# Sheet_1_2025-08-11.net
KiCad netlist of a schematic drawn in Altium Designer
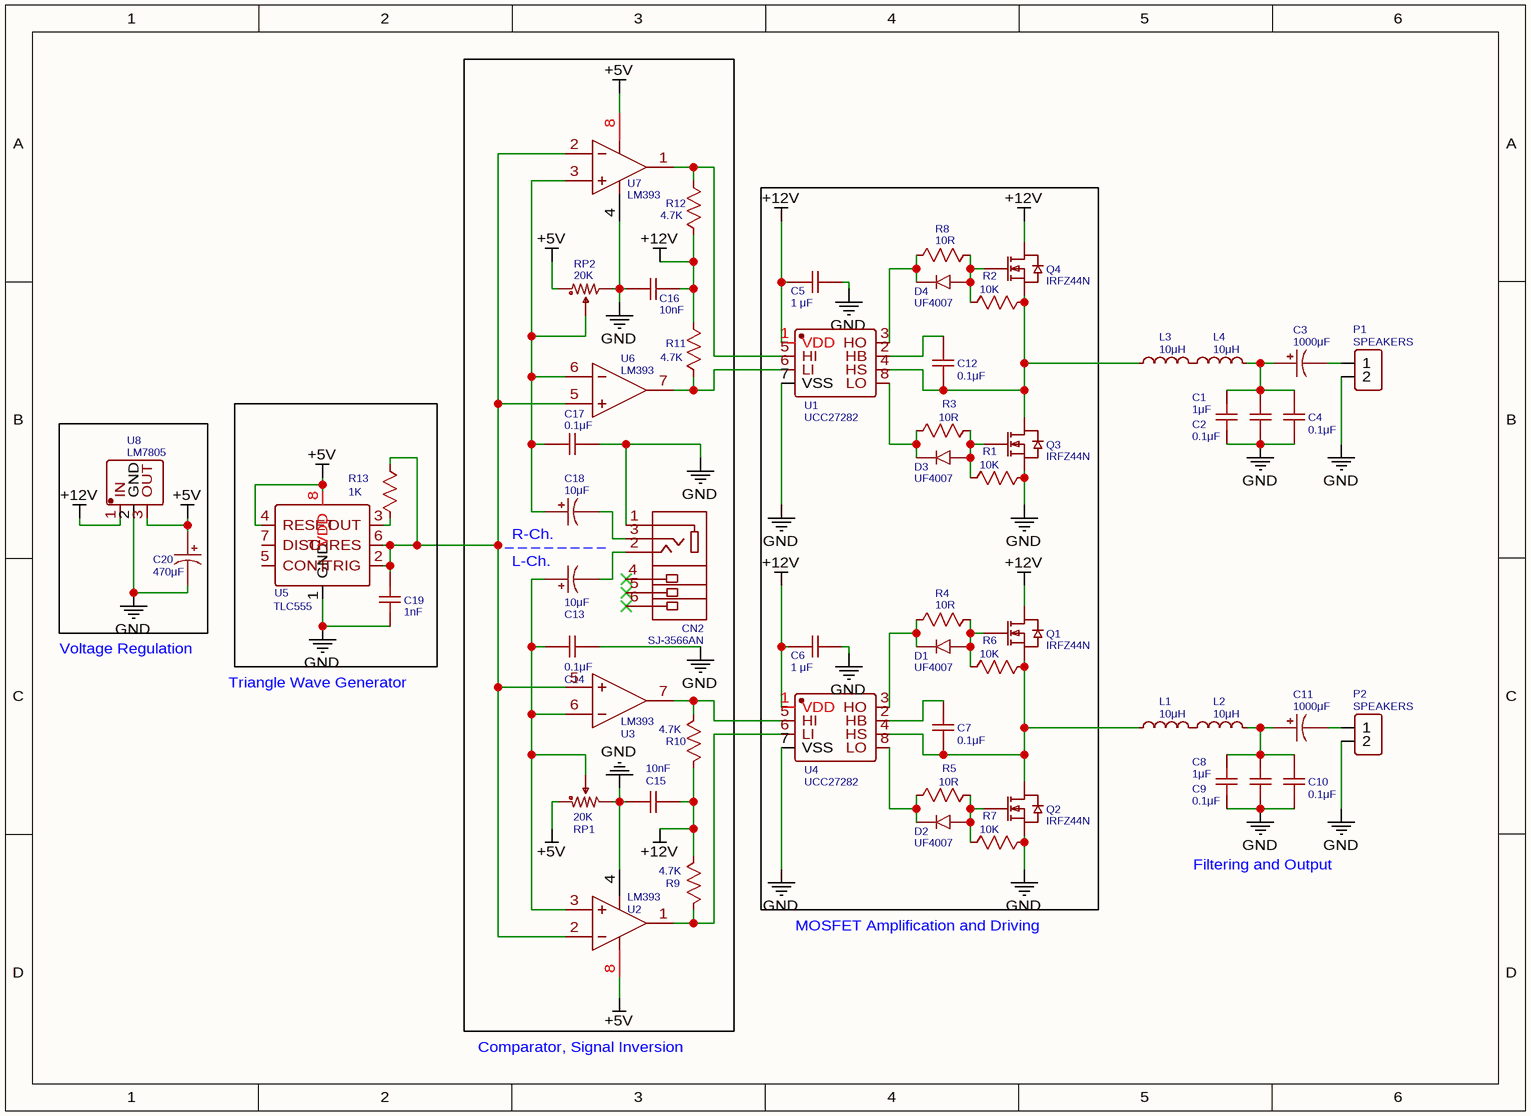
[diagram p0: Sheet_1_2025-08-11.schdoc]

(export (version "E")
  (design (tool "Eeschema 10.0.6"))
  (components
    (comp (ref "C1")
      (value "1μF")
      (fields (field (name "CONTRIBUTOR") "LCEDA_Lib"))
      (libsource (lib "altium-import") (part "root_3_1μF_"))
    )
    (comp (ref "C2")
      (value "0.1μF")
      (fields (field (name "CONTRIBUTOR") "LCEDA_Lib"))
      (libsource (lib "altium-import") (part "root_3_0.1μF_"))
    )
    (comp (ref "C3")
      (value "1000μF")
      (fields (field (name "CONTRIBUTOR") "LCEDA_Lib"))
      (libsource (lib "altium-import") (part "root_0_1000μF_"))
    )
    (comp (ref "C4")
      (value "0.1μF")
      (fields (field (name "CONTRIBUTOR") "LCEDA_Lib"))
      (libsource (lib "altium-import") (part "root_1_0.1μF_"))
    )
    (comp (ref "C5")
      (value "1 μF")
      (fields (field (name "CONTRIBUTOR") "LCEDA_Lib"))
      (libsource (lib "altium-import") (part "root_0_1 μF_"))
    )
    (comp (ref "C6")
      (value "1 μF")
      (fields (field (name "CONTRIBUTOR") "LCEDA_Lib"))
      (libsource (lib "altium-import") (part "root_0_1 μF_"))
    )
    (comp (ref "C7")
      (value "0.1μF")
      (fields (field (name "CONTRIBUTOR") "LCEDA_Lib"))
      (libsource (lib "altium-import") (part "root_1_0.1μF_"))
    )
    (comp (ref "C8")
      (value "1μF")
      (fields (field (name "CONTRIBUTOR") "LCEDA_Lib"))
      (libsource (lib "altium-import") (part "root_3_1μF_"))
    )
    (comp (ref "C9")
      (value "0.1μF")
      (fields (field (name "CONTRIBUTOR") "LCEDA_Lib"))
      (libsource (lib "altium-import") (part "root_3_0.1μF_"))
    )
    (comp (ref "C10")
      (value "0.1μF")
      (fields (field (name "CONTRIBUTOR") "LCEDA_Lib"))
      (libsource (lib "altium-import") (part "root_1_0.1μF_"))
    )
    (comp (ref "C11")
      (value "1000μF")
      (fields (field (name "CONTRIBUTOR") "LCEDA_Lib"))
      (libsource (lib "altium-import") (part "root_0_1000μF_"))
    )
    (comp (ref "C12")
      (value "0.1μF")
      (fields (field (name "CONTRIBUTOR") "LCEDA_Lib"))
      (libsource (lib "altium-import") (part "root_1_0.1μF_"))
    )
    (comp (ref "C13")
      (value "10μF")
      (fields (field (name "CONTRIBUTOR") "LCEDA_Lib"))
      (libsource (lib "") (part "root_0_10μF__1"))
    )
    (comp (ref "C14")
      (value "0.1μF")
      (fields (field (name "CONTRIBUTOR") "LCEDA_Lib"))
      (libsource (lib "altium-import") (part "root_2_0.1μF_"))
    )
    (comp (ref "C15")
      (value "10nF")
      (fields (field (name "CONTRIBUTOR") "LCEDA_Lib"))
      (libsource (lib "") (part "root_2_10nF__1"))
    )
    (comp (ref "C16")
      (value "10nF")
      (fields (field (name "CONTRIBUTOR") "LCEDA_Lib"))
      (libsource (lib "altium-import") (part "root_2_10nF_"))
    )
    (comp (ref "C17")
      (value "0.1μF")
      (fields (field (name "CONTRIBUTOR") "LCEDA_Lib"))
      (libsource (lib "") (part "root_2_0.1μF__1"))
    )
    (comp (ref "C18")
      (value "10μF")
      (fields (field (name "CONTRIBUTOR") "LCEDA_Lib"))
      (libsource (lib "altium-import") (part "root_0_10μF_"))
    )
    (comp (ref "C19")
      (value "1nF")
      (fields (field (name "CONTRIBUTOR") "LCEDA_Lib"))
      (libsource (lib "altium-import") (part "root_1_1nF_"))
    )
    (comp (ref "C20")
      (value "470μF")
      (fields (field (name "CONTRIBUTOR") "LCEDA_Lib"))
      (libsource (lib "altium-import") (part "root_3_470μF_"))
    )
    (comp (ref "CN2")
      (value "SJ-3566AN")
      (fields (field (name "MANUFACTURER") "CUI") (field (name "CONTRIBUTOR") "lcsc"))
      (libsource (lib "altium-import") (part "root_0_SJ-3566AN_"))
    )
    (comp (ref "D1")
      (value "UF4007")
      (fields (field (name "MANUFACTURER") "STARSEA") (field (name "CONTRIBUTOR") "立创EDA官方封装库"))
      (libsource (lib "altium-import") (part "root_2_UF4007_"))
    )
    (comp (ref "D2")
      (value "UF4007")
      (fields (field (name "MANUFACTURER") "STARSEA") (field (name "CONTRIBUTOR") "立创EDA官方封装库"))
      (libsource (lib "altium-import") (part "root_2_UF4007_"))
    )
    (comp (ref "D3")
      (value "UF4007")
      (fields (field (name "MANUFACTURER") "STARSEA") (field (name "CONTRIBUTOR") "立创EDA官方封装库"))
      (libsource (lib "altium-import") (part "root_2_UF4007_"))
    )
    (comp (ref "D4")
      (value "UF4007")
      (fields (field (name "MANUFACTURER") "STARSEA") (field (name "CONTRIBUTOR") "立创EDA官方封装库"))
      (libsource (lib "altium-import") (part "root_2_UF4007_"))
    )
    (comp (ref "L1")
      (value "10μH")
      (fields (field (name "CONTRIBUTOR") "LCEDA_Lib"))
      (libsource (lib "altium-import") (part "root_0_10μH_"))
    )
    (comp (ref "L2")
      (value "10μH")
      (fields (field (name "CONTRIBUTOR") "LCEDA_Lib"))
      (libsource (lib "altium-import") (part "root_0_10μH_"))
    )
    (comp (ref "L3")
      (value "10μH")
      (fields (field (name "CONTRIBUTOR") "LCEDA_Lib"))
      (libsource (lib "altium-import") (part "root_0_10μH_"))
    )
    (comp (ref "L4")
      (value "10μH")
      (fields (field (name "CONTRIBUTOR") "LCEDA_Lib"))
      (libsource (lib "altium-import") (part "root_0_10μH_"))
    )
    (comp (ref "P1")
      (value "SPEAKERS")
      (fields (field (name "CONTRIBUTOR") "LCEDA_Lib"))
      (libsource (lib "altium-import") (part "root_0_SPEAKERS_"))
    )
    (comp (ref "P2")
      (value "SPEAKERS")
      (fields (field (name "CONTRIBUTOR") "LCEDA_Lib"))
      (libsource (lib "altium-import") (part "root_0_SPEAKERS_"))
    )
    (comp (ref "Q1")
      (value "IRFZ44N")
      (fields (field (name "MANUFACTURER") "IR") (field (name "MANUFACTURER PART") "IRFZ44NPBF"))
      (libsource (lib "altium-import") (part "root_0_IRFZ44N_"))
    )
    (comp (ref "Q2")
      (value "IRFZ44N")
      (fields (field (name "MANUFACTURER") "IR") (field (name "MANUFACTURER PART") "IRFZ44NPBF"))
      (libsource (lib "altium-import") (part "root_0_IRFZ44N_"))
    )
    (comp (ref "Q3")
      (value "IRFZ44N")
      (fields (field (name "MANUFACTURER") "IR") (field (name "MANUFACTURER PART") "IRFZ44NPBF"))
      (libsource (lib "altium-import") (part "root_0_IRFZ44N_"))
    )
    (comp (ref "Q4")
      (value "IRFZ44N")
      (fields (field (name "MANUFACTURER") "IR") (field (name "MANUFACTURER PART") "IRFZ44NPBF"))
      (libsource (lib "altium-import") (part "root_0_IRFZ44N_"))
    )
    (comp (ref "R1")
      (value "10K")
      (fields (field (name "CONTRIBUTOR") "LCEDA_Lib"))
      (libsource (lib "altium-import") (part "root_0_10K_"))
    )
    (comp (ref "R2")
      (value "10K")
      (fields (field (name "CONTRIBUTOR") "LCEDA_Lib"))
      (libsource (lib "altium-import") (part "root_0_10K_"))
    )
    (comp (ref "R3")
      (value "10R")
      (fields (field (name "CONTRIBUTOR") "LCEDA_Lib"))
      (libsource (lib "altium-import") (part "root_2_10R_"))
    )
    (comp (ref "R4")
      (value "10R")
      (fields (field (name "CONTRIBUTOR") "LCEDA_Lib"))
      (libsource (lib "altium-import") (part "root_2_10R_"))
    )
    (comp (ref "R5")
      (value "10R")
      (fields (field (name "CONTRIBUTOR") "LCEDA_Lib"))
      (libsource (lib "altium-import") (part "root_2_10R_"))
    )
    (comp (ref "R6")
      (value "10K")
      (fields (field (name "CONTRIBUTOR") "LCEDA_Lib"))
      (libsource (lib "altium-import") (part "root_0_10K_"))
    )
    (comp (ref "R7")
      (value "10K")
      (fields (field (name "CONTRIBUTOR") "LCEDA_Lib"))
      (libsource (lib "altium-import") (part "root_0_10K_"))
    )
    (comp (ref "R8")
      (value "10R")
      (fields (field (name "CONTRIBUTOR") "LCEDA_Lib"))
      (libsource (lib "altium-import") (part "root_2_10R_"))
    )
    (comp (ref "R9")
      (value "4.7K")
      (fields (field (name "CONTRIBUTOR") "LCEDA_Lib"))
      (libsource (lib "") (part "root_3_4.7K__1"))
    )
    (comp (ref "R10")
      (value "4.7K")
      (fields (field (name "CONTRIBUTOR") "LCEDA_Lib"))
      (libsource (lib "") (part "root_3_4.7K__1"))
    )
    (comp (ref "R11")
      (value "4.7K")
      (fields (field (name "CONTRIBUTOR") "LCEDA_Lib"))
      (libsource (lib "altium-import") (part "root_3_4.7K_"))
    )
    (comp (ref "R12")
      (value "4.7K")
      (fields (field (name "CONTRIBUTOR") "LCEDA_Lib"))
      (libsource (lib "altium-import") (part "root_3_4.7K_"))
    )
    (comp (ref "R13")
      (value "1K")
      (fields (field (name "CONTRIBUTOR") "LCEDA_Lib"))
      (libsource (lib "altium-import") (part "root_1_1K_"))
    )
    (comp (ref "RP1")
      (value "20K")
      (fields (field (name "CONTRIBUTOR") "LCEDA_Lib"))
      (libsource (lib "") (part "root_2_20K__1"))
    )
    (comp (ref "RP2")
      (value "20K")
      (fields (field (name "CONTRIBUTOR") "LCEDA_Lib"))
      (libsource (lib "altium-import") (part "root_2_20K_"))
    )
    (comp (ref "U1")
      (value "UCC27282")
      (fields
        (field (name "MANUFACTURER") "Texas Instruments")
        (field (name "MANUFACTURER PART") "UCC27200DR")
        (field (name "CONTRIBUTOR") "Electric_Evan")
      )
      (libsource (lib "altium-import") (part "root_0_UCC27282_"))
    )
    (comp (ref "U2")
      (value "LM393")
      (fields
        (field (name "MANUFACTURER") "TI")
        (field (name "MANUFACTURER PART") "LM393P")
        (field (name "SUBPART_NO") "1")
      )
      (libsource (lib "altium-import") (part "root_0_LM393_"))
    )
    (comp (ref "U3")
      (value "LM393")
      (fields
        (field (name "MANUFACTURER") "TI")
        (field (name "MANUFACTURER PART") "LM393P")
        (field (name "SUBPART_NO") "1")
      )
      (libsource (lib "") (part "root_0_LM393__2"))
    )
    (comp (ref "U4")
      (value "UCC27282")
      (fields
        (field (name "MANUFACTURER") "Texas Instruments")
        (field (name "MANUFACTURER PART") "UCC27200DR")
        (field (name "CONTRIBUTOR") "Electric_Evan")
      )
      (libsource (lib "altium-import") (part "root_0_UCC27282_"))
    )
    (comp (ref "U5")
      (value "TLC555")
      (fields
        (field (name "MANUFACTURER") "TI(德州仪器)")
        (field (name "MANUFACTURER PART") "TLC555CP")
        (field (name "CONTRIBUTOR") "Electric_Evan")
      )
      (libsource (lib "altium-import") (part "root_0_TLC555_"))
    )
    (comp (ref "U6")
      (value "LM393")
      (fields
        (field (name "MANUFACTURER") "TI")
        (field (name "MANUFACTURER PART") "LM393P")
        (field (name "SUBPART_NO") "1")
      )
      (libsource (lib "") (part "root_0_LM393__3"))
    )
    (comp (ref "U7")
      (value "LM393")
      (fields
        (field (name "MANUFACTURER") "TI")
        (field (name "MANUFACTURER PART") "LM393P")
        (field (name "SUBPART_NO") "1")
      )
      (libsource (lib "") (part "root_0_LM393__1"))
    )
    (comp (ref "U8")
      (value "LM7805")
      (fields (field (name "MANUFACTURER") "FAIRCHILD") (field (name "MANUFACTURER PART") "LM7805CT"))
      (libsource (lib "altium-import") (part "root_1_LM7805_"))
    )
  )
  (nets
    (net (code "1") (name "+5V") (class "Default")
      (node (ref "C20") (pin "1") (pinfunction "1_1") (pintype "passive"))
      (node (ref "RP1") (pin "1") (pinfunction "1_1") (pintype "passive"))
      (node (ref "RP2") (pin "1") (pinfunction "1_1") (pintype "passive"))
      (node (ref "U2") (pin "8") (pinfunction "VCC_8") (pintype "passive"))
      (node (ref "U5") (pin "4") (pinfunction "RESET_4") (pintype "passive"))
      (node (ref "U5") (pin "8") (pinfunction "VDD_8") (pintype "passive"))
      (node (ref "U7") (pin "8") (pinfunction "VCC_8") (pintype "passive"))
      (node (ref "U8") (pin "3") (pinfunction "OUT_3") (pintype "passive"))
    )
    (net (code "2") (name "+12V") (class "Default")
      (node (ref "C15") (pin "1") (pinfunction "1_1") (pintype "passive"))
      (node (ref "C16") (pin "1") (pinfunction "1_1") (pintype "passive"))
      (node (ref "C5") (pin "1") (pinfunction "1_1") (pintype "passive"))
      (node (ref "C6") (pin "1") (pinfunction "1_1") (pintype "passive"))
      (node (ref "Q1") (pin "2") (pinfunction "D_2") (pintype "passive"))
      (node (ref "Q4") (pin "2") (pinfunction "D_2") (pintype "passive"))
      (node (ref "R10") (pin "1") (pinfunction "1_1") (pintype "passive"))
      (node (ref "R11") (pin "1") (pinfunction "1_1") (pintype "passive"))
      (node (ref "R12") (pin "2") (pinfunction "2_2") (pintype "passive"))
      (node (ref "R9") (pin "2") (pinfunction "2_2") (pintype "passive"))
      (node (ref "U1") (pin "1") (pinfunction "VDD_1") (pintype "passive"))
      (node (ref "U4") (pin "1") (pinfunction "VDD_1") (pintype "passive"))
      (node (ref "U8") (pin "1") (pinfunction "IN_1") (pintype "passive"))
    )
    (net (code "3") (name "GND") (class "Default")
      (node (ref "C1") (pin "2") (pinfunction "2_2") (pintype "passive"))
      (node (ref "C10") (pin "1") (pinfunction "1_1") (pintype "passive"))
      (node (ref "C14") (pin "1") (pinfunction "1_1") (pintype "passive"))
      (node (ref "C15") (pin "2") (pinfunction "2_2") (pintype "passive"))
      (node (ref "C16") (pin "2") (pinfunction "2_2") (pintype "passive"))
      (node (ref "C17") (pin "1") (pinfunction "1_1") (pintype "passive"))
      (node (ref "C19") (pin "1") (pinfunction "1_1") (pintype "passive"))
      (node (ref "C2") (pin "2") (pinfunction "2_2") (pintype "passive"))
      (node (ref "C20") (pin "2") (pinfunction "2_2") (pintype "passive"))
      (node (ref "C4") (pin "1") (pinfunction "1_1") (pintype "passive"))
      (node (ref "C5") (pin "2") (pinfunction "2_2") (pintype "passive"))
      (node (ref "C6") (pin "2") (pinfunction "2_2") (pintype "passive"))
      (node (ref "C8") (pin "2") (pinfunction "2_2") (pintype "passive"))
      (node (ref "C9") (pin "2") (pinfunction "2_2") (pintype "passive"))
      (node (ref "CN2") (pin "1") (pinfunction "1_1") (pintype "passive"))
      (node (ref "P1") (pin "2") (pinfunction "2_2") (pintype "passive"))
      (node (ref "P2") (pin "2") (pinfunction "2_2") (pintype "passive"))
      (node (ref "Q2") (pin "3") (pinfunction "S_3") (pintype "passive"))
      (node (ref "Q3") (pin "3") (pinfunction "S_3") (pintype "passive"))
      (node (ref "R1") (pin "2") (pinfunction "2_2") (pintype "passive"))
      (node (ref "R7") (pin "2") (pinfunction "2_2") (pintype "passive"))
      (node (ref "RP1") (pin "3") (pinfunction "3_3") (pintype "passive"))
      (node (ref "RP2") (pin "3") (pinfunction "3_3") (pintype "passive"))
      (node (ref "U1") (pin "7") (pinfunction "VSS_7") (pintype "passive"))
      (node (ref "U2") (pin "4") (pinfunction "GND_4") (pintype "passive"))
      (node (ref "U4") (pin "7") (pinfunction "VSS_7") (pintype "passive"))
      (node (ref "U5") (pin "1") (pinfunction "GND_1") (pintype "passive"))
      (node (ref "U7") (pin "4") (pinfunction "GND_4") (pintype "passive"))
      (node (ref "U8") (pin "2") (pinfunction "GND_2") (pintype "passive"))
    )
    (net (code "4") (name "Net-(C1-Pad1)") (class "Default")
      (node (ref "C1") (pin "1") (pinfunction "1_1") (pintype "passive"))
      (node (ref "C2") (pin "1") (pinfunction "1_1") (pintype "passive"))
      (node (ref "C3") (pin "1") (pinfunction "1_1") (pintype "passive"))
      (node (ref "C4") (pin "2") (pinfunction "2_2") (pintype "passive"))
      (node (ref "L4") (pin "2") (pinfunction "2_2") (pintype "passive"))
    )
    (net (code "5") (name "Net-(C3-Pad2)") (class "Default")
      (node (ref "C3") (pin "2") (pinfunction "2_2") (pintype "passive"))
      (node (ref "P1") (pin "1") (pinfunction "1_1") (pintype "passive"))
    )
    (net (code "6") (name "Net-(C10-Pad2)") (class "Default")
      (node (ref "C10") (pin "2") (pinfunction "2_2") (pintype "passive"))
      (node (ref "C11") (pin "1") (pinfunction "1_1") (pintype "passive"))
      (node (ref "C8") (pin "1") (pinfunction "1_1") (pintype "passive"))
      (node (ref "C9") (pin "1") (pinfunction "1_1") (pintype "passive"))
      (node (ref "L2") (pin "2") (pinfunction "2_2") (pintype "passive"))
    )
    (net (code "7") (name "Net-(C11-Pad2)") (class "Default")
      (node (ref "C11") (pin "2") (pinfunction "2_2") (pintype "passive"))
      (node (ref "P2") (pin "1") (pinfunction "1_1") (pintype "passive"))
    )
    (net (code "8") (name "Net-(C13-Pad2)") (class "Default")
      (node (ref "C13") (pin "2") (pinfunction "2_2") (pintype "passive"))
      (node (ref "CN2") (pin "2") (pinfunction "2_2") (pintype "passive"))
    )
    (net (code "9") (name "Net-(C18-Pad2)") (class "Default")
      (node (ref "C18") (pin "2") (pinfunction "2_2") (pintype "passive"))
      (node (ref "CN2") (pin "3") (pinfunction "3_3") (pintype "passive"))
    )
    (net (code "10") (name "Net-(D1-A)") (class "Default")
      (node (ref "D1") (pin "1") (pinfunction "A_1") (pintype "passive"))
      (node (ref "Q1") (pin "1") (pinfunction "G_1") (pintype "passive"))
      (node (ref "R4") (pin "1") (pinfunction "1_1") (pintype "passive"))
      (node (ref "R6") (pin "1") (pinfunction "1_1") (pintype "passive"))
    )
    (net (code "11") (name "Net-(D1-C)") (class "Default")
      (node (ref "D1") (pin "2") (pinfunction "C_2") (pintype "passive"))
      (node (ref "R4") (pin "2") (pinfunction "2_2") (pintype "passive"))
      (node (ref "U4") (pin "3") (pinfunction "HO_3") (pintype "passive"))
    )
    (net (code "12") (name "Net-(D2-A)") (class "Default")
      (node (ref "D2") (pin "1") (pinfunction "A_1") (pintype "passive"))
      (node (ref "Q2") (pin "1") (pinfunction "G_1") (pintype "passive"))
      (node (ref "R5") (pin "1") (pinfunction "1_1") (pintype "passive"))
      (node (ref "R7") (pin "1") (pinfunction "1_1") (pintype "passive"))
    )
    (net (code "13") (name "Net-(D2-C)") (class "Default")
      (node (ref "D2") (pin "2") (pinfunction "C_2") (pintype "passive"))
      (node (ref "R5") (pin "2") (pinfunction "2_2") (pintype "passive"))
      (node (ref "U4") (pin "8") (pinfunction "LO_8") (pintype "passive"))
    )
    (net (code "14") (name "Net-(D3-A)") (class "Default")
      (node (ref "D3") (pin "1") (pinfunction "A_1") (pintype "passive"))
      (node (ref "Q3") (pin "1") (pinfunction "G_1") (pintype "passive"))
      (node (ref "R1") (pin "1") (pinfunction "1_1") (pintype "passive"))
      (node (ref "R3") (pin "1") (pinfunction "1_1") (pintype "passive"))
    )
    (net (code "15") (name "Net-(D3-C)") (class "Default")
      (node (ref "D3") (pin "2") (pinfunction "C_2") (pintype "passive"))
      (node (ref "R3") (pin "2") (pinfunction "2_2") (pintype "passive"))
      (node (ref "U1") (pin "8") (pinfunction "LO_8") (pintype "passive"))
    )
    (net (code "16") (name "Net-(D4-A)") (class "Default")
      (node (ref "D4") (pin "1") (pinfunction "A_1") (pintype "passive"))
      (node (ref "Q4") (pin "1") (pinfunction "G_1") (pintype "passive"))
      (node (ref "R2") (pin "1") (pinfunction "1_1") (pintype "passive"))
      (node (ref "R8") (pin "1") (pinfunction "1_1") (pintype "passive"))
    )
    (net (code "17") (name "Net-(D4-C)") (class "Default")
      (node (ref "D4") (pin "2") (pinfunction "C_2") (pintype "passive"))
      (node (ref "R8") (pin "2") (pinfunction "2_2") (pintype "passive"))
      (node (ref "U1") (pin "3") (pinfunction "HO_3") (pintype "passive"))
    )
    (net (code "18") (name "Net-(L1-Pad2)") (class "Default")
      (node (ref "L1") (pin "2") (pinfunction "2_2") (pintype "passive"))
      (node (ref "L2") (pin "1") (pinfunction "1_1") (pintype "passive"))
    )
    (net (code "19") (name "Net-(L3-Pad2)") (class "Default")
      (node (ref "L3") (pin "2") (pinfunction "2_2") (pintype "passive"))
      (node (ref "L4") (pin "1") (pinfunction "1_1") (pintype "passive"))
    )
    (net (code "20") (name "Net-(Q1-S)") (class "Default")
      (node (ref "C7") (pin "1") (pinfunction "1_1") (pintype "passive"))
      (node (ref "L1") (pin "1") (pinfunction "1_1") (pintype "passive"))
      (node (ref "Q1") (pin "3") (pinfunction "S_3") (pintype "passive"))
      (node (ref "Q2") (pin "2") (pinfunction "D_2") (pintype "passive"))
      (node (ref "R6") (pin "2") (pinfunction "2_2") (pintype "passive"))
      (node (ref "U4") (pin "4") (pinfunction "HS_4") (pintype "passive"))
    )
    (net (code "21") (name "Net-(Q3-D)") (class "Default")
      (node (ref "C12") (pin "1") (pinfunction "1_1") (pintype "passive"))
      (node (ref "L3") (pin "1") (pinfunction "1_1") (pintype "passive"))
      (node (ref "Q3") (pin "2") (pinfunction "D_2") (pintype "passive"))
      (node (ref "Q4") (pin "3") (pinfunction "S_3") (pintype "passive"))
      (node (ref "R2") (pin "2") (pinfunction "2_2") (pintype "passive"))
      (node (ref "U1") (pin "4") (pinfunction "HS_4") (pintype "passive"))
    )
    (net (code "22") (name "Net-(U1-HB)") (class "Default")
      (node (ref "C12") (pin "2") (pinfunction "2_2") (pintype "passive"))
      (node (ref "U1") (pin "2") (pinfunction "HB_2") (pintype "passive"))
    )
    (net (code "23") (name "Net-(U1-HI)") (class "Default")
      (node (ref "R12") (pin "1") (pinfunction "1_1") (pintype "passive"))
      (node (ref "U1") (pin "5") (pinfunction "HI_5") (pintype "passive"))
      (node (ref "U7") (pin "1") (pinfunction "1OUT_1") (pintype "passive"))
    )
    (net (code "24") (name "Net-(U1-LI)") (class "Default")
      (node (ref "R11") (pin "2") (pinfunction "2_2") (pintype "passive"))
      (node (ref "U1") (pin "6") (pinfunction "LI_6") (pintype "passive"))
      (node (ref "U6") (pin "7") (pinfunction "2OUT_7") (pintype "passive"))
    )
    (net (code "25") (name "Net-(U2-1IN+)") (class "Default")
      (node (ref "C13") (pin "1") (pinfunction "1_1") (pintype "passive"))
      (node (ref "C14") (pin "2") (pinfunction "2_2") (pintype "passive"))
      (node (ref "RP1") (pin "2") (pinfunction "2_2") (pintype "passive"))
      (node (ref "U2") (pin "3") (pinfunction "1IN+_3") (pintype "passive"))
      (node (ref "U3") (pin "6") (pinfunction "2IN-_6") (pintype "passive"))
    )
    (net (code "26") (name "Net-(U2-1IN-)") (class "Default")
      (node (ref "C19") (pin "2") (pinfunction "2_2") (pintype "passive"))
      (node (ref "R13") (pin "2") (pinfunction "2_2") (pintype "passive"))
      (node (ref "U2") (pin "2") (pinfunction "1IN-_2") (pintype "passive"))
      (node (ref "U3") (pin "5") (pinfunction "2IN+_5") (pintype "passive"))
      (node (ref "U5") (pin "2") (pinfunction "TRIG_2") (pintype "passive"))
      (node (ref "U5") (pin "6") (pinfunction "THRES_6") (pintype "passive"))
      (node (ref "U6") (pin "5") (pinfunction "2IN+_5") (pintype "passive"))
      (node (ref "U7") (pin "2") (pinfunction "1IN-_2") (pintype "passive"))
    )
    (net (code "27") (name "Net-(U2-1OUT)") (class "Default")
      (node (ref "R9") (pin "1") (pinfunction "1_1") (pintype "passive"))
      (node (ref "U2") (pin "1") (pinfunction "1OUT_1") (pintype "passive"))
      (node (ref "U4") (pin "6") (pinfunction "LI_6") (pintype "passive"))
    )
    (net (code "28") (name "Net-(U3-2OUT)") (class "Default")
      (node (ref "R10") (pin "2") (pinfunction "2_2") (pintype "passive"))
      (node (ref "U3") (pin "7") (pinfunction "2OUT_7") (pintype "passive"))
      (node (ref "U4") (pin "5") (pinfunction "HI_5") (pintype "passive"))
    )
    (net (code "29") (name "Net-(U4-HB)") (class "Default")
      (node (ref "C7") (pin "2") (pinfunction "2_2") (pintype "passive"))
      (node (ref "U4") (pin "2") (pinfunction "HB_2") (pintype "passive"))
    )
    (net (code "30") (name "Net-(U5-OUT)") (class "Default")
      (node (ref "R13") (pin "1") (pinfunction "1_1") (pintype "passive"))
      (node (ref "U5") (pin "3") (pinfunction "OUT_3") (pintype "passive"))
    )
    (net (code "31") (name "Net-(U6-2IN-)") (class "Default")
      (node (ref "C17") (pin "2") (pinfunction "2_2") (pintype "passive"))
      (node (ref "C18") (pin "1") (pinfunction "1_1") (pintype "passive"))
      (node (ref "RP2") (pin "2") (pinfunction "2_2") (pintype "passive"))
      (node (ref "U6") (pin "6") (pinfunction "2IN-_6") (pintype "passive"))
      (node (ref "U7") (pin "3") (pinfunction "1IN+_3") (pintype "passive"))
    )
    (net (code "32") (name "unconnected-(CN2-Pad4)") (class "Default")
      (node (ref "CN2") (pin "4") (pinfunction "4_4") (pintype "passive"))
    )
    (net (code "33") (name "unconnected-(CN2-Pad5)") (class "Default")
      (node (ref "CN2") (pin "5") (pinfunction "5_5") (pintype "passive+no_connect"))
    )
    (net (code "34") (name "unconnected-(CN2-Pad6)") (class "Default")
      (node (ref "CN2") (pin "6") (pinfunction "6_6") (pintype "passive+no_connect"))
    )
    (net (code "35") (name "unconnected-(U5-CONT-Pad5)") (class "Default")
      (node (ref "U5") (pin "5") (pinfunction "CONT_5") (pintype "passive"))
    )
    (net (code "36") (name "unconnected-(U5-DISC-Pad7)") (class "Default")
      (node (ref "U5") (pin "7") (pinfunction "DISC_7") (pintype "passive"))
    )
  )
)
